# CH32V307RCT6-R1.net
KiCad netlist of a schematic drawn in Altium Designer
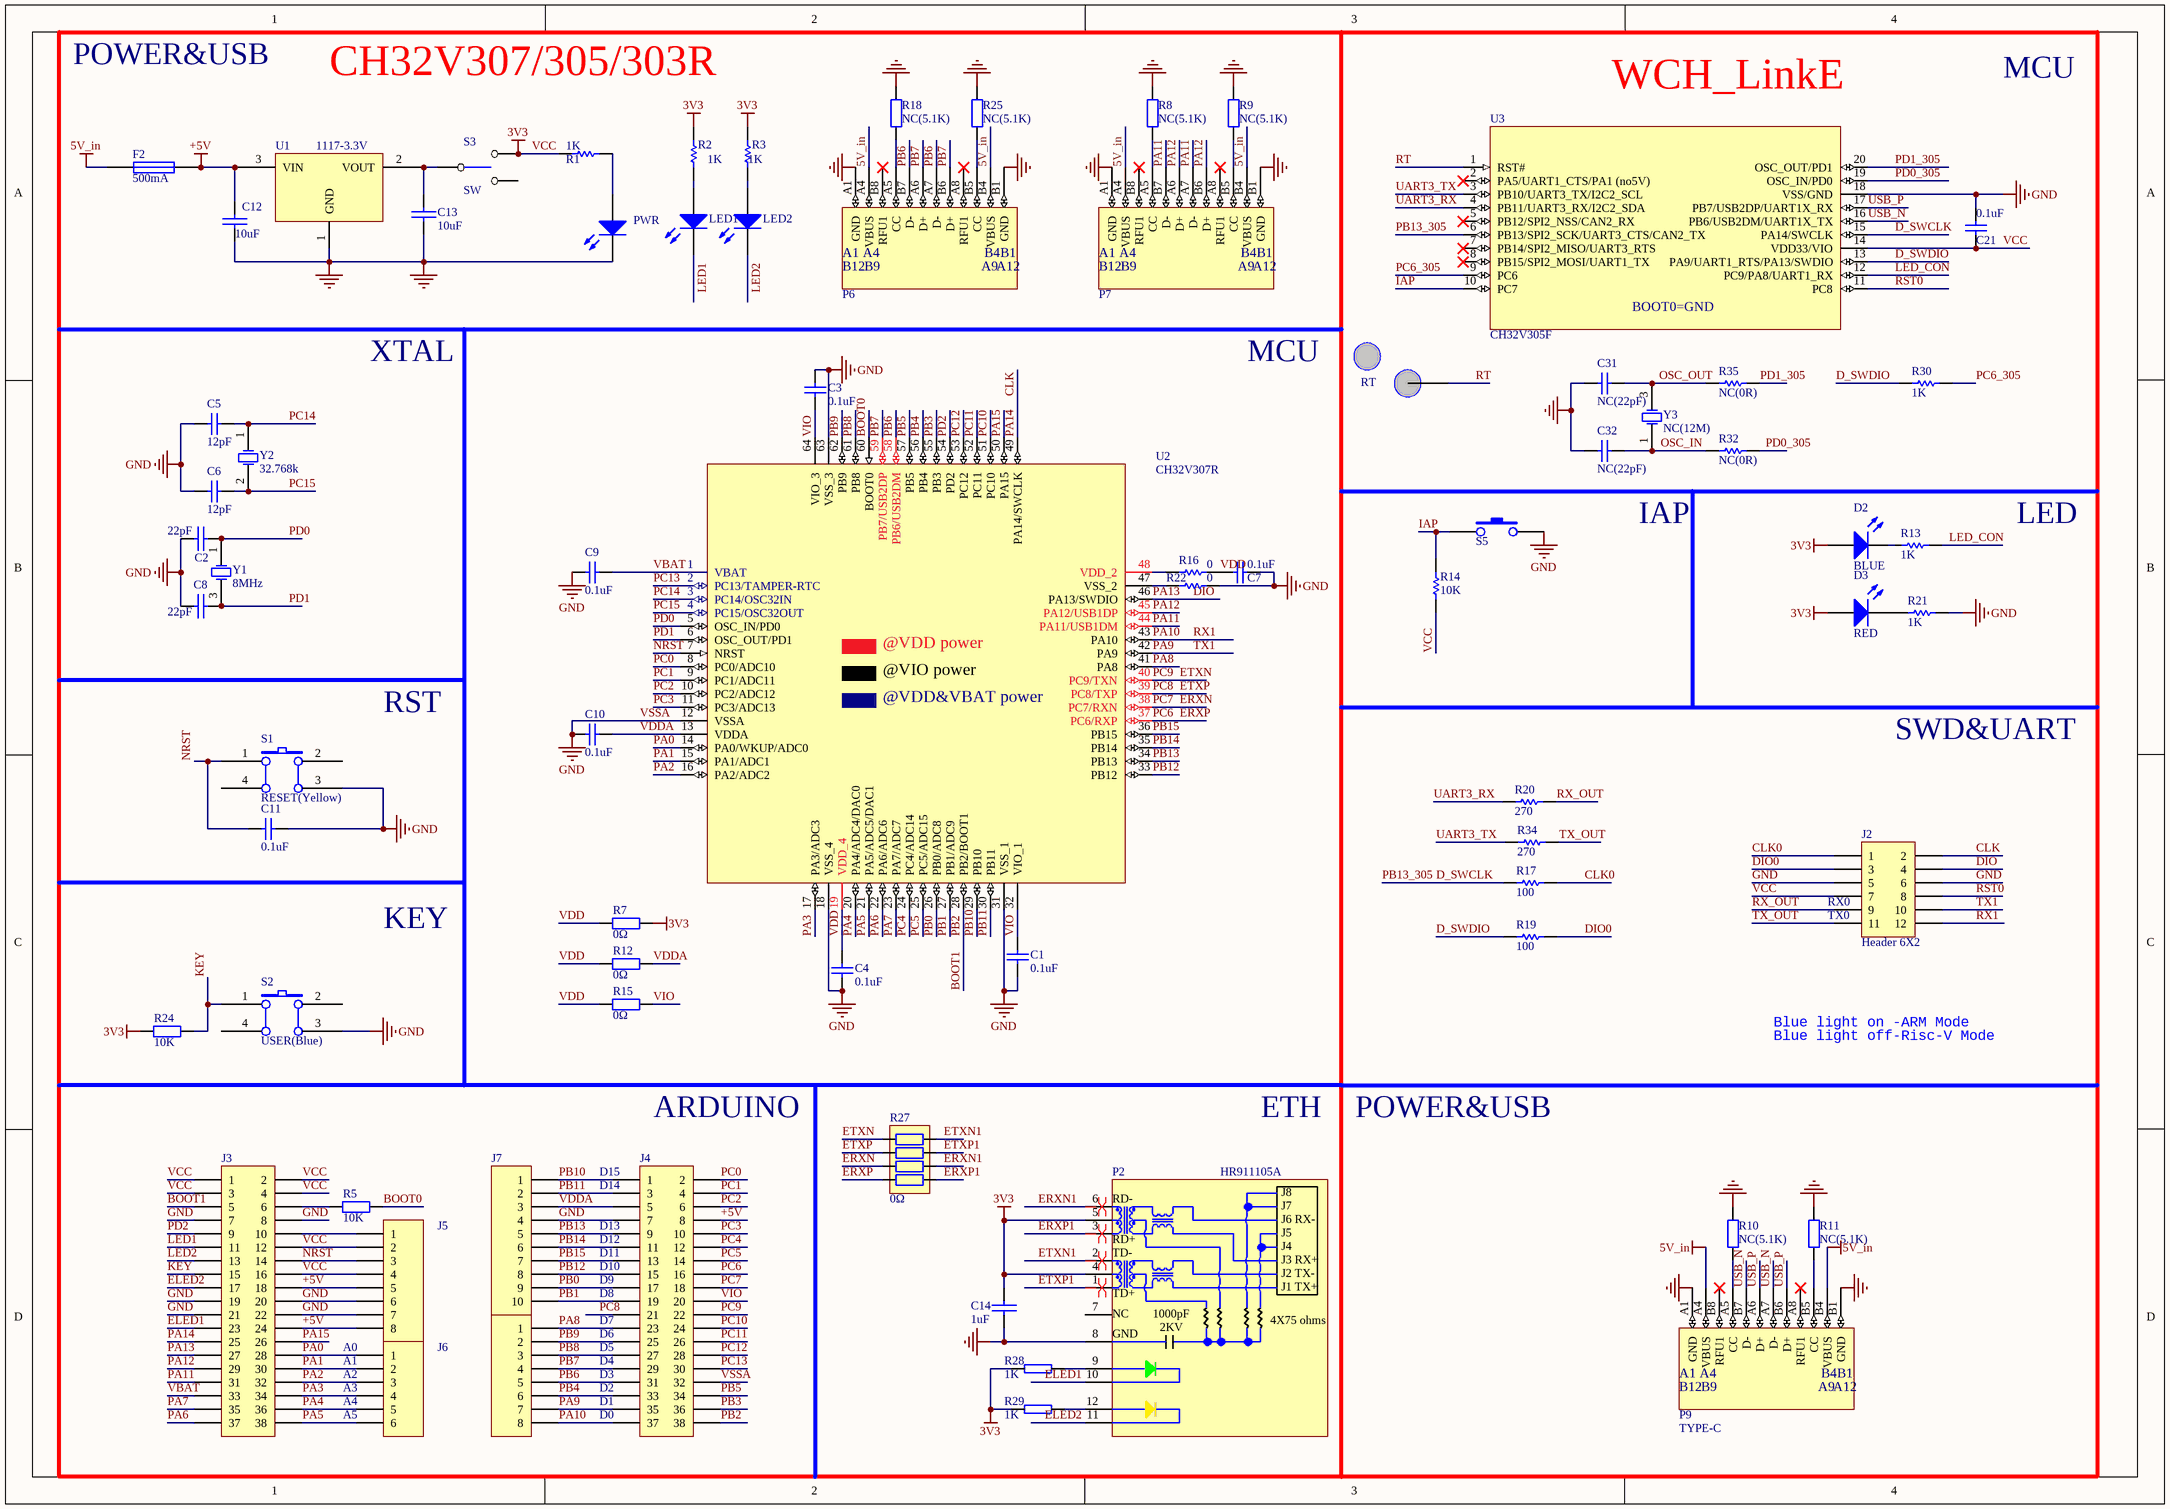
[diagram p0: CH32V307RCT6-R1.SchDoc]

(export (version "E")
  (design (tool "Eeschema 10.0.6"))
  (components
    (comp (ref "C1")
      (value "0.1uF")
      (footprint "0603_C")
      (description "Capacitor")
      (libsource (lib "Miscellaneous Devices") (part "Cap"))
    )
    (comp (ref "C2")
      (value "22pF")
      (footprint "0603_C")
      (description "Capacitor")
      (libsource (lib "*") (part "CAP"))
    )
    (comp (ref "C3")
      (value "0.1uF")
      (footprint "0603_C")
      (description "Capacitor")
      (libsource (lib "Miscellaneous Devices") (part "Cap"))
    )
    (comp (ref "C4")
      (value "0.1uF")
      (footprint "0603_C")
      (description "Capacitor")
      (libsource (lib "Miscellaneous Devices") (part "Cap"))
    )
    (comp (ref "C5")
      (value "12pF")
      (footprint "0603_C")
      (description "Capacitor")
      (libsource (lib "Miscellaneous Devices") (part "Cap"))
    )
    (comp (ref "C6")
      (value "12pF")
      (footprint "0603_C")
      (description "Capacitor")
      (libsource (lib "Miscellaneous Devices") (part "Cap"))
    )
    (comp (ref "C7")
      (value "0.1uF")
      (footprint "0603_C")
      (description "Capacitor")
      (libsource (lib "Miscellaneous Devices") (part "Cap"))
    )
    (comp (ref "C8")
      (value "22pF")
      (footprint "0603_C")
      (description "Capacitor")
      (libsource (lib "*") (part "CAP"))
    )
    (comp (ref "C9")
      (value "0.1uF")
      (footprint "0603_C")
      (description "Capacitor")
      (libsource (lib "Miscellaneous Devices") (part "Cap"))
    )
    (comp (ref "C10")
      (value "0.1uF")
      (footprint "0603_C")
      (description "Capacitor")
      (libsource (lib "Miscellaneous Devices") (part "Cap"))
    )
    (comp (ref "C11")
      (value "0.1uF")
      (footprint "0603_C")
      (description "Capacitor")
      (libsource (lib "Miscellaneous Devices") (part "Cap"))
    )
    (comp (ref "C12")
      (value "10uF")
      (footprint "3216_C")
      (description "Capacitor")
      (libsource (lib "*") (part "CAP"))
    )
    (comp (ref "C13")
      (value "10uF")
      (footprint "3216_C")
      (description "Capacitor")
      (libsource (lib "*") (part "CAP"))
    )
    (comp (ref "C14")
      (value "1uF")
      (footprint "0603_C")
      (description "Capacitor")
      (libsource (lib "*") (part "CAP"))
    )
    (comp (ref "C21")
      (value "0.1uF")
      (footprint "0603_C")
      (description "Capacitor")
      (libsource (lib "Miscellaneous Devices") (part "Cap"))
    )
    (comp (ref "C31")
      (value "NC(22pF)")
      (footprint "0603_C")
      (description "Capacitor")
      (fields (field (name "PUBLISHER") "Altium Limited"))
      (libsource (lib "*") (part "Cap"))
    )
    (comp (ref "C32")
      (value "NC(22pF)")
      (footprint "0603_C")
      (description "Capacitor")
      (fields (field (name "PUBLISHER") "Altium Limited"))
      (libsource (lib "*") (part "Cap"))
    )
    (comp (ref "D2")
      (value "BLUE")
      (footprint "0603+")
      (description "Typical RED, GREEN, YELLOW, AMBER GaAs LED")
      (fields (field (name "PUBLISHER") "Altium Limited"))
      (libsource (lib "MYLIB") (part "D0603"))
    )
    (comp (ref "D3")
      (value "RED")
      (footprint "0603+")
      (description "Typical RED, GREEN, YELLOW, AMBER GaAs LED")
      (fields (field (name "PUBLISHER") "Altium Limited"))
      (libsource (lib "MYLIB") (part "D0603"))
    )
    (comp (ref "F2")
      (value "500mA")
      (footprint "0805")
      (description "Fuse")
      (libsource (lib "*") (part "FUSE1"))
    )
    (comp (ref "J2")
      (value "Header 6X2")
      (footprint "IDC12-2.54mm")
      (description "Header, 6-Pin, Dual row")
      (fields (field (name "PUBLISHER") "Altium Limited"))
      (libsource (lib "Miscellaneous Connectors") (part "Header 6X2"))
    )
    (comp (ref "J3")
      (value "Header 19X2")
      (footprint "IDC38-2.54mm")
      (description "Header, 19-Pin, Dual row")
      (fields (field (name "PUBLISHER") "Altium Limited"))
      (libsource (lib "Miscellaneous Connectors") (part "Header 19X2"))
    )
    (comp (ref "J4")
      (value "Header 19X2")
      (footprint "IDC38-2.54mm")
      (description "Header, 19-Pin, Dual row")
      (fields (field (name "PUBLISHER") "Altium Limited"))
      (libsource (lib "Miscellaneous Connectors") (part "Header 19X2"))
    )
    (comp (ref "J5")
      (value "Header 8")
      (footprint "SIP8-2.54mm")
      (description "Header, 8-Pin")
      (fields (field (name "PUBLISHER") "Altium Limited"))
      (libsource (lib "Miscellaneous Connectors") (part "Header 8"))
    )
    (comp (ref "J6")
      (value "Header 6")
      (footprint "SIP6-2.54MM")
      (description "Header, 6-Pin")
      (fields (field (name "PUBLISHER") "Altium Limited"))
      (libsource (lib "Miscellaneous Connectors") (part "Header 6"))
    )
    (comp (ref "J7")
      (value "Header 10")
      (footprint "SIP10-2.54mm")
      (description "Header, 10-Pin")
      (fields (field (name "PUBLISHER") "Altium Limited"))
      (libsource (lib "Miscellaneous Connectors") (part "Header 10"))
    )
    (comp (ref "J8")
      (value "Header 8")
      (footprint "SIP8-2.54mm")
      (description "Header, 8-Pin")
      (fields (field (name "PUBLISHER") "Altium Limited"))
      (libsource (lib "") (part "Header 8_1"))
    )
    (comp (ref "LED1")
      (value "LED1   blue")
      (footprint "0603+")
      (description "Typical INFRARED GaAs LED")
      (fields (field (name "PUBLISHER") "Altium Limited"))
      (libsource (lib "Miscellaneous Devices") (part "LED0"))
    )
    (comp (ref "LED2")
      (value "LED2  blue")
      (footprint "0603+")
      (description "Typical INFRARED GaAs LED")
      (fields (field (name "PUBLISHER") "Altium Limited"))
      (libsource (lib "Miscellaneous Devices") (part "LED0"))
    )
    (comp (ref "P2") (value "HR911105A") (footprint "HR911105A") (libsource (lib "*") (part "HR911105A")))
    (comp (ref "P6")
      (value "TYPE-C")
      (footprint "TYPE-C-Receptacle-2.0")
      (libsource (lib "*") (part "TYPE-C1"))
    )
    (comp (ref "P7")
      (value "TYPE-C")
      (footprint "TYPE-C-Receptacle-2.0")
      (libsource (lib "*") (part "TYPE-C1"))
    )
    (comp (ref "P9")
      (value "TYPE-C")
      (footprint "TYPE-C-Receptacle-2.0")
      (libsource (lib "*") (part "TYPE-C1"))
    )
    (comp (ref "PWR")
      (value "POWER  red")
      (footprint "0603+")
      (description "Typical INFRARED GaAs LED")
      (fields (field (name "PUBLISHER") "Altium Limited"))
      (libsource (lib "Miscellaneous Devices") (part "LED0"))
    )
    (comp (ref "R1")
      (value "1K")
      (footprint "0603")
      (description "Semiconductor Resistor")
      (libsource (lib "Miscellaneous Devices") (part "Res Semi"))
    )
    (comp (ref "R2")
      (value "1K")
      (footprint "0603")
      (description "Semiconductor Resistor")
      (libsource (lib "Miscellaneous Devices") (part "Res Semi"))
    )
    (comp (ref "R3")
      (value "1K")
      (footprint "0603")
      (description "Semiconductor Resistor")
      (libsource (lib "Miscellaneous Devices") (part "Res Semi"))
    )
    (comp (ref "R5")
      (value "10K")
      (footprint "0603")
      (description "Resistor")
      (libsource (lib "") (part "Res2_3"))
    )
    (comp (ref "R7")
      (value "0Ω")
      (footprint "0603")
      (description "Resistor")
      (libsource (lib "Miscellaneous Devices") (part "Res2"))
    )
    (comp (ref "R8")
      (value "NC(5.1K)")
      (footprint "0603")
      (description "Resistor")
      (libsource (lib "") (part "Res2_2"))
    )
    (comp (ref "R9")
      (value "NC(5.1K)")
      (footprint "0603")
      (description "Resistor")
      (libsource (lib "") (part "Res2_2"))
    )
    (comp (ref "R10")
      (value "NC(5.1K)")
      (footprint "0603")
      (description "Resistor")
      (libsource (lib "") (part "Res2_1"))
    )
    (comp (ref "R11")
      (value "NC(5.1K)")
      (footprint "0603")
      (description "Resistor")
      (libsource (lib "") (part "Res2_1"))
    )
    (comp (ref "R12")
      (value "0Ω")
      (footprint "0603")
      (description "Resistor")
      (libsource (lib "Miscellaneous Devices") (part "Res2"))
    )
    (comp (ref "R13")
      (value "1K")
      (footprint "0603")
      (description "Resistor")
      (fields (field (name "PUBLISHER") "Altium Limited"))
      (libsource (lib "MYLIB") (part "0603-1"))
    )
    (comp (ref "R14")
      (value "10K")
      (footprint "0603")
      (description "Resistor")
      (fields (field (name "PUBLISHER") "Altium Limited"))
      (libsource (lib "MYLIB") (part "0603-1"))
    )
    (comp (ref "R15")
      (value "0Ω")
      (footprint "0603")
      (description "Resistor")
      (libsource (lib "Miscellaneous Devices") (part "Res2"))
    )
    (comp (ref "R16")
      (value "0")
      (footprint "0603")
      (description "Resistor")
      (fields (field (name "PUBLISHER") "Altium Limited"))
      (libsource (lib "MYLIB") (part "0603-1"))
    )
    (comp (ref "R17")
      (value "100")
      (footprint "0603")
      (description "Resistor")
      (fields (field (name "PUBLISHER") "Altium Limited"))
      (libsource (lib "MYLIB") (part "0603-1"))
    )
    (comp (ref "R18")
      (value "NC(5.1K)")
      (footprint "0603")
      (description "Resistor")
      (libsource (lib "") (part "Res2_2"))
    )
    (comp (ref "R19")
      (value "100")
      (footprint "0603")
      (description "Resistor")
      (fields (field (name "PUBLISHER") "Altium Limited"))
      (libsource (lib "MYLIB") (part "0603-1"))
    )
    (comp (ref "R20")
      (value "270")
      (footprint "0603")
      (description "Resistor")
      (fields (field (name "PUBLISHER") "Altium Limited"))
      (libsource (lib "MYLIB") (part "0603-1"))
    )
    (comp (ref "R21")
      (value "1K")
      (footprint "0603")
      (description "Resistor")
      (fields (field (name "PUBLISHER") "Altium Limited"))
      (libsource (lib "MYLIB") (part "0603-1"))
    )
    (comp (ref "R22")
      (value "0")
      (footprint "0603")
      (description "Resistor")
      (fields (field (name "PUBLISHER") "Altium Limited"))
      (libsource (lib "MYLIB") (part "0603-1"))
    )
    (comp (ref "R24")
      (value "10K")
      (footprint "0603")
      (description "Resistor")
      (libsource (lib "Miscellaneous Devices") (part "Res2"))
    )
    (comp (ref "R25")
      (value "NC(5.1K)")
      (footprint "0603")
      (description "Resistor")
      (libsource (lib "") (part "Res2_2"))
    )
    (comp (ref "R27")
      (value "0Ω")
      (footprint "8P4R-0603")
      (description "贴片网络排阻")
      (fields (field (name "版权归属") "源创客"))
      (libsource (lib "wch_sch_others") (part "R-8P4R"))
    )
    (comp (ref "R28") (value "1K") (footprint "0603") (libsource (lib "wch_sch_others") (part "RES")))
    (comp (ref "R29") (value "1K") (footprint "0603") (libsource (lib "wch_sch_others") (part "RES")))
    (comp (ref "R30")
      (value "1K")
      (footprint "0603")
      (description "Resistor")
      (fields (field (name "PUBLISHER") "Altium Limited"))
      (libsource (lib "MYLIB") (part "0603-1"))
    )
    (comp (ref "R32")
      (value "NC(0R)")
      (footprint "0603")
      (description "Resistor")
      (fields (field (name "PUBLISHER") "Altium Limited"))
      (libsource (lib "MYLIB") (part "0603-1"))
    )
    (comp (ref "R34")
      (value "270")
      (footprint "0603")
      (description "Resistor")
      (fields (field (name "PUBLISHER") "Altium Limited"))
      (libsource (lib "MYLIB") (part "0603-1"))
    )
    (comp (ref "R35")
      (value "NC(0R)")
      (footprint "0603")
      (description "Resistor")
      (fields (field (name "PUBLISHER") "Altium Limited"))
      (libsource (lib "MYLIB") (part "0603-1"))
    )
    (comp (ref "RT")
      (value "Testpoint")
      (footprint "TESTPOINT1")
      (description "测试点")
      (libsource (lib "wch_sch_others") (part "Testpoint"))
    )
    (comp (ref "S1")
      (value "RESET(Yellow)")
      (footprint "KEYX")
      (description "SE PUSHBUTTON")
      (libsource (lib "Documents") (part "SW PUSHBUTTON"))
    )
    (comp (ref "S2")
      (value "USER(Blue)")
      (footprint "KEYX")
      (description "SE PUSHBUTTON")
      (libsource (lib "Documents") (part "SW PUSHBUTTON"))
    )
    (comp (ref "S3") (value "SW") (footprint "SW1") (libsource (lib "MYSCH") (part "SW")))
    (comp (ref "S5") (value "KEY") (footprint "贴片按键") (libsource (lib "*") (part "KEY")))
    (comp (ref "U1")
      (value "1117-3.3V")
      (footprint "SOT-223")
      (libsource (lib "wch_sch_others") (part "1117-3.3V"))
    )
    (comp (ref "U2")
      (value "CH32V307R")
      (footprint "LQFP64M_10x10")
      (description "RISC-V FPU HD-MCU, 144MHz, USB_480M, USB OTG, 1000M Ethernet MAC, 2*CAN")
      (libsource (lib "CHXXX") (part "CH32V307R"))
    )
    (comp (ref "U3")
      (value "CH32V305F")
      (footprint "TSSOP20")
      (description "RISC-V FPU HD-MCU, 144MHz, USB_480M, CAN, UART*2, SPI")
      (libsource (lib "CHXXX") (part "CH32V305F"))
    )
    (comp (ref "Y1")
      (value "8MHz")
      (footprint "XT3225")
      (description "Crystal Oscillator")
      (fields (field (name "PUBLISHER") "Altium Limited"))
      (libsource (lib "*") (part "XTAL"))
    )
    (comp (ref "Y2")
      (value "32.768k")
      (footprint "FC-135")
      (description "Crystal Oscillator")
      (fields (field (name "PUBLISHER") "Altium Limited"))
      (libsource (lib "Miscellaneous Devices") (part "XTAL"))
    )
    (comp (ref "Y3")
      (value "NC(12M)")
      (footprint "XT3225")
      (description "Crystal Oscillator")
      (libsource (lib "*") (part "XTAL"))
    )
  )
  (nets
    (net (code "1") (name "+5V") (class "Default")
      (node (ref "C12") (pin "1") (pinfunction "1_1") (pintype "passive"))
      (node (ref "F2") (pin "2") (pinfunction "2_2") (pintype "passive"))
      (node (ref "J3") (pin "18") (pinfunction "18_18") (pintype "passive"))
      (node (ref "J3") (pin "24") (pinfunction "24_24") (pintype "passive"))
      (node (ref "J4") (pin "8") (pinfunction "8_8") (pintype "passive"))
      (node (ref "J5") (pin "5") (pinfunction "5_5") (pintype "passive"))
      (node (ref "J5") (pin "8") (pinfunction "8_8") (pintype "passive"))
      (node (ref "U1") (pin "3") (pinfunction "VIN_3") (pintype "passive"))
    )
    (net (code "2") (name "/BOOT0") (class "Default")
      (node (ref "R5") (pin "2") (pinfunction "2_2") (pintype "passive"))
      (node (ref "U2") (pin "60") (pinfunction "BOOT0_60") (pintype "input"))
    )
    (net (code "3") (name "/BOOT1") (class "Default")
      (node (ref "J3") (pin "5") (pinfunction "5_5") (pintype "passive"))
      (node (ref "J4") (pin "38") (pinfunction "38_38") (pintype "passive"))
      (node (ref "U2") (pin "28") (pinfunction "PB2/BOOT1_28") (pintype "bidirectional"))
    )
    (net (code "4") (name "/CLK") (class "Default")
      (node (ref "J2") (pin "2") (pinfunction "2_2") (pintype "passive"))
      (node (ref "J3") (pin "25") (pinfunction "25_25") (pintype "passive"))
      (node (ref "U2") (pin "49") (pinfunction "PA14/SWCLK_49") (pintype "bidirectional"))
    )
    (net (code "5") (name "/CLK0") (class "Default")
      (node (ref "J2") (pin "1") (pinfunction "1_1") (pintype "passive"))
      (node (ref "R17") (pin "1") (pinfunction "1_1") (pintype "passive"))
    )
    (net (code "6") (name "/DIO") (class "Default")
      (node (ref "J2") (pin "4") (pinfunction "4_4") (pintype "passive"))
      (node (ref "J3") (pin "27") (pinfunction "27_27") (pintype "passive"))
      (node (ref "U2") (pin "46") (pinfunction "PA13/SWDIO_46") (pintype "bidirectional"))
    )
    (net (code "7") (name "/DIO0") (class "Default")
      (node (ref "J2") (pin "3") (pinfunction "3_3") (pintype "passive"))
      (node (ref "R19") (pin "1") (pinfunction "1_1") (pintype "passive"))
    )
    (net (code "8") (name "/D_SWCLK") (class "Default")
      (node (ref "R17") (pin "2") (pinfunction "2_2") (pintype "passive"))
      (node (ref "U3") (pin "15") (pinfunction "PA14/SWCLK_15") (pintype "bidirectional"))
      (node (ref "U3") (pin "6") (pinfunction "PB13/SPI2_SCK/UART3_CTS/CAN2_TX_6") (pintype "bidirectional"))
    )
    (net (code "9") (name "/D_SWDIO") (class "Default")
      (node (ref "R19") (pin "2") (pinfunction "2_2") (pintype "passive"))
      (node (ref "R30") (pin "1") (pinfunction "1_1") (pintype "passive"))
      (node (ref "U3") (pin "13") (pinfunction "PA9/UART1_RTS/PA13/SWDIO_13") (pintype "bidirectional"))
    )
    (net (code "10") (name "/ELED1") (class "Default")
      (node (ref "J3") (pin "23") (pinfunction "23_23") (pintype "passive"))
      (node (ref "P2") (pin "10") (pintype "passive"))
    )
    (net (code "11") (name "/ELED2") (class "Default")
      (node (ref "J3") (pin "17") (pinfunction "17_17") (pintype "passive"))
      (node (ref "P2") (pin "11") (pintype "passive"))
    )
    (net (code "12") (name "/ERXN") (class "Default")
      (node (ref "J4") (pin "18") (pinfunction "18_18") (pintype "passive"))
      (node (ref "R27") (pin "3") (pinfunction "3_3") (pintype "passive"))
      (node (ref "U2") (pin "38") (pinfunction "PC7/RXN_38") (pintype "bidirectional"))
    )
    (net (code "13") (name "/ERXN1") (class "Default")
      (node (ref "P2") (pin "6") (pintype "passive"))
      (node (ref "R27") (pin "6") (pinfunction "6_6") (pintype "passive"))
    )
    (net (code "14") (name "/ERXP") (class "Default")
      (node (ref "J4") (pin "16") (pinfunction "16_16") (pintype "passive"))
      (node (ref "R27") (pin "4") (pinfunction "4_4") (pintype "passive"))
      (node (ref "U2") (pin "37") (pinfunction "PC6/RXP_37") (pintype "bidirectional"))
    )
    (net (code "15") (name "/ERXP1") (class "Default")
      (node (ref "P2") (pin "3") (pintype "passive"))
      (node (ref "R27") (pin "5") (pinfunction "5_5") (pintype "passive"))
    )
    (net (code "16") (name "/ETXN") (class "Default")
      (node (ref "J4") (pin "22") (pinfunction "22_22") (pintype "passive"))
      (node (ref "R27") (pin "1") (pinfunction "1_1") (pintype "passive"))
      (node (ref "U2") (pin "40") (pinfunction "PC9/TXN_40") (pintype "bidirectional"))
    )
    (net (code "17") (name "/ETXN1") (class "Default")
      (node (ref "P2") (pin "2") (pintype "passive"))
      (node (ref "R27") (pin "8") (pinfunction "8_8") (pintype "passive"))
    )
    (net (code "18") (name "/ETXP") (class "Default")
      (node (ref "J4") (pin "21") (pinfunction "21_21") (pintype "passive"))
      (node (ref "R27") (pin "2") (pinfunction "2_2") (pintype "passive"))
      (node (ref "U2") (pin "39") (pinfunction "PC8/TXP_39") (pintype "bidirectional"))
    )
    (net (code "19") (name "/ETXP1") (class "Default")
      (node (ref "P2") (pin "1") (pintype "passive"))
      (node (ref "R27") (pin "7") (pinfunction "7_7") (pintype "passive"))
    )
    (net (code "20") (name "/IAP") (class "Default")
      (node (ref "R14") (pin "1") (pinfunction "1_1") (pintype "passive"))
      (node (ref "S5") (pin "1") (pinfunction "1_1") (pintype "passive"))
      (node (ref "U3") (pin "10") (pinfunction "PC7_10") (pintype "bidirectional"))
    )
    (net (code "21") (name "/KEY") (class "Default")
      (node (ref "J3") (pin "15") (pinfunction "15_15") (pintype "passive"))
      (node (ref "R24") (pin "1") (pinfunction "1_1") (pintype "passive"))
      (node (ref "S2") (pin "1") (pinfunction "A0_1") (pintype "passive"))
    )
    (net (code "22") (name "/LED1") (class "Default")
      (node (ref "J3") (pin "11") (pinfunction "11_11") (pintype "passive"))
      (node (ref "LED1") (pin "2") (pinfunction "K_2") (pintype "passive"))
    )
    (net (code "23") (name "/LED2") (class "Default")
      (node (ref "J3") (pin "13") (pinfunction "13_13") (pintype "passive"))
      (node (ref "LED2") (pin "2") (pinfunction "K_2") (pintype "passive"))
    )
    (net (code "24") (name "/LED_CON") (class "Default")
      (node (ref "R13") (pin "1") (pinfunction "1_1") (pintype "passive"))
      (node (ref "U3") (pin "12") (pinfunction "PC9/PA8/UART1_RX_12") (pintype "bidirectional"))
    )
    (net (code "25") (name "/NRST") (class "Default")
      (node (ref "C11") (pin "2") (pinfunction "2_2") (pintype "passive"))
      (node (ref "J3") (pin "14") (pinfunction "14_14") (pintype "passive"))
      (node (ref "J5") (pin "3") (pinfunction "3_3") (pintype "passive"))
      (node (ref "S1") (pin "1") (pinfunction "A0_1") (pintype "passive"))
      (node (ref "U2") (pin "7") (pinfunction "NRST_7") (pintype "input"))
    )
    (net (code "26") (name "/OSC_IN") (class "Default")
      (node (ref "C32") (pin "2") (pinfunction "2_2") (pintype "passive"))
      (node (ref "R32") (pin "2") (pinfunction "2_2") (pintype "passive"))
      (node (ref "Y3") (pin "1") (pinfunction "OSC1_1") (pintype "passive"))
    )
    (net (code "27") (name "/OSC_OUT") (class "Default")
      (node (ref "C31") (pin "2") (pinfunction "2_2") (pintype "passive"))
      (node (ref "R35") (pin "2") (pinfunction "2_2") (pintype "passive"))
      (node (ref "Y3") (pin "3") (pinfunction "OSC2_3") (pintype "passive"))
    )
    (net (code "28") (name "/PA0") (class "Default")
      (node (ref "J3") (pin "28") (pinfunction "28_28") (pintype "passive"))
      (node (ref "J6") (pin "1") (pinfunction "1_1") (pintype "passive"))
      (node (ref "U2") (pin "14") (pinfunction "PA0/WKUP/ADC0_14") (pintype "bidirectional"))
    )
    (net (code "29") (name "/PA1") (class "Default")
      (node (ref "J3") (pin "30") (pinfunction "30_30") (pintype "passive"))
      (node (ref "J6") (pin "2") (pinfunction "2_2") (pintype "passive"))
      (node (ref "U2") (pin "15") (pinfunction "PA1/ADC1_15") (pintype "bidirectional"))
    )
    (net (code "30") (name "/PA2") (class "Default")
      (node (ref "J3") (pin "32") (pinfunction "32_32") (pintype "passive"))
      (node (ref "J6") (pin "3") (pinfunction "3_3") (pintype "passive"))
      (node (ref "U2") (pin "16") (pinfunction "PA2/ADC2_16") (pintype "bidirectional"))
    )
    (net (code "31") (name "/PA3") (class "Default")
      (node (ref "J3") (pin "34") (pinfunction "34_34") (pintype "passive"))
      (node (ref "J6") (pin "4") (pinfunction "4_4") (pintype "passive"))
      (node (ref "U2") (pin "17") (pinfunction "PA3/ADC3_17") (pintype "bidirectional"))
    )
    (net (code "32") (name "/PA4") (class "Default")
      (node (ref "J3") (pin "36") (pinfunction "36_36") (pintype "passive"))
      (node (ref "J6") (pin "5") (pinfunction "5_5") (pintype "passive"))
      (node (ref "U2") (pin "20") (pinfunction "PA4/ADC4/DAC0_20") (pintype "bidirectional"))
    )
    (net (code "33") (name "/PA5") (class "Default")
      (node (ref "J3") (pin "38") (pinfunction "38_38") (pintype "passive"))
      (node (ref "J6") (pin "6") (pinfunction "6_6") (pintype "passive"))
      (node (ref "U2") (pin "21") (pinfunction "PA5/ADC5/DAC1_21") (pintype "bidirectional"))
    )
    (net (code "34") (name "/PA6") (class "Default")
      (node (ref "J3") (pin "37") (pinfunction "37_37") (pintype "passive"))
      (node (ref "U2") (pin "22") (pinfunction "PA6/ADC6_22") (pintype "bidirectional"))
    )
    (net (code "35") (name "/PA7") (class "Default")
      (node (ref "J3") (pin "35") (pinfunction "35_35") (pintype "passive"))
      (node (ref "U2") (pin "23") (pinfunction "PA7/ADC7_23") (pintype "bidirectional"))
    )
    (net (code "36") (name "/PA8") (class "Default")
      (node (ref "J4") (pin "23") (pinfunction "23_23") (pintype "passive"))
      (node (ref "J8") (pin "1") (pinfunction "1_1") (pintype "passive"))
      (node (ref "U2") (pin "41") (pinfunction "PA8_41") (pintype "bidirectional"))
    )
    (net (code "37") (name "/PA9") (class "Default")
      (node (ref "J2") (pin "10") (pinfunction "10_10") (pintype "passive"))
      (node (ref "J4") (pin "35") (pinfunction "35_35") (pintype "passive"))
      (node (ref "J8") (pin "7") (pinfunction "7_7") (pintype "passive"))
      (node (ref "U2") (pin "42") (pinfunction "PA9_42") (pintype "bidirectional"))
    )
    (net (code "38") (name "/PA10") (class "Default")
      (node (ref "J2") (pin "12") (pinfunction "12_12") (pintype "passive"))
      (node (ref "J4") (pin "37") (pinfunction "37_37") (pintype "passive"))
      (node (ref "J8") (pin "8") (pinfunction "8_8") (pintype "passive"))
      (node (ref "U2") (pin "43") (pinfunction "PA10_43") (pintype "bidirectional"))
    )
    (net (code "39") (name "/PA11") (class "Default")
      (node (ref "J3") (pin "31") (pinfunction "31_31") (pintype "passive"))
      (node (ref "P7") (pin "A7") (pinfunction "D-_A7") (pintype "bidirectional"))
      (node (ref "P7") (pin "B7") (pinfunction "D-_B7") (pintype "bidirectional"))
      (node (ref "U2") (pin "44") (pinfunction "PA11/USB1DM_44") (pintype "bidirectional"))
    )
    (net (code "40") (name "/PA12") (class "Default")
      (node (ref "J3") (pin "29") (pinfunction "29_29") (pintype "passive"))
      (node (ref "P7") (pin "A6") (pinfunction "D+_A6") (pintype "bidirectional"))
      (node (ref "P7") (pin "B6") (pinfunction "D+_B6") (pintype "bidirectional"))
      (node (ref "U2") (pin "45") (pinfunction "PA12/USB1DP_45") (pintype "bidirectional"))
    )
    (net (code "41") (name "/PA15") (class "Default")
      (node (ref "J3") (pin "26") (pinfunction "26_26") (pintype "passive"))
      (node (ref "U2") (pin "50") (pinfunction "PA15_50") (pintype "bidirectional"))
    )
    (net (code "42") (name "/PB0") (class "Default")
      (node (ref "J4") (pin "17") (pinfunction "17_17") (pintype "passive"))
      (node (ref "J7") (pin "9") (pinfunction "9_9") (pintype "passive"))
      (node (ref "U2") (pin "26") (pinfunction "PB0/ADC8_26") (pintype "bidirectional"))
    )
    (net (code "43") (name "/PB1") (class "Default")
      (node (ref "J4") (pin "19") (pinfunction "19_19") (pintype "passive"))
      (node (ref "J7") (pin "10") (pinfunction "10_10") (pintype "passive"))
      (node (ref "U2") (pin "27") (pinfunction "PB1/ADC9_27") (pintype "bidirectional"))
    )
    (net (code "44") (name "/PB3") (class "Default")
      (node (ref "J4") (pin "36") (pinfunction "36_36") (pintype "passive"))
      (node (ref "U2") (pin "55") (pinfunction "PB3_55") (pintype "bidirectional"))
    )
    (net (code "45") (name "/PB4") (class "Default")
      (node (ref "J4") (pin "33") (pinfunction "33_33") (pintype "passive"))
      (node (ref "J8") (pin "6") (pinfunction "6_6") (pintype "passive"))
      (node (ref "U2") (pin "56") (pinfunction "PB4_56") (pintype "bidirectional"))
    )
    (net (code "46") (name "/PB5") (class "Default")
      (node (ref "J4") (pin "34") (pinfunction "34_34") (pintype "passive"))
      (node (ref "U2") (pin "57") (pinfunction "PB5_57") (pintype "bidirectional"))
    )
    (net (code "47") (name "/PB6") (class "Default")
      (node (ref "J4") (pin "31") (pinfunction "31_31") (pintype "passive"))
      (node (ref "J8") (pin "5") (pinfunction "5_5") (pintype "passive"))
      (node (ref "P6") (pin "A7") (pinfunction "D-_A7") (pintype "bidirectional"))
      (node (ref "P6") (pin "B7") (pinfunction "D-_B7") (pintype "bidirectional"))
      (node (ref "U2") (pin "58") (pinfunction "PB6/USB2DM_58") (pintype "bidirectional"))
    )
    (net (code "48") (name "/PB7") (class "Default")
      (node (ref "J4") (pin "29") (pinfunction "29_29") (pintype "passive"))
      (node (ref "J8") (pin "4") (pinfunction "4_4") (pintype "passive"))
      (node (ref "P6") (pin "A6") (pinfunction "D+_A6") (pintype "bidirectional"))
      (node (ref "P6") (pin "B6") (pinfunction "D+_B6") (pintype "bidirectional"))
      (node (ref "U2") (pin "59") (pinfunction "PB7/USB2DP_59") (pintype "bidirectional"))
    )
    (net (code "49") (name "/PB8") (class "Default")
      (node (ref "J4") (pin "27") (pinfunction "27_27") (pintype "passive"))
      (node (ref "J8") (pin "3") (pinfunction "3_3") (pintype "passive"))
      (node (ref "U2") (pin "61") (pinfunction "PB8_61") (pintype "bidirectional"))
    )
    (net (code "50") (name "/PB9") (class "Default")
      (node (ref "J4") (pin "25") (pinfunction "25_25") (pintype "passive"))
      (node (ref "J8") (pin "2") (pinfunction "2_2") (pintype "passive"))
      (node (ref "U2") (pin "62") (pinfunction "PB9_62") (pintype "bidirectional"))
    )
    (net (code "51") (name "/PB10") (class "Default")
      (node (ref "J4") (pin "1") (pinfunction "1_1") (pintype "passive"))
      (node (ref "J7") (pin "1") (pinfunction "1_1") (pintype "passive"))
      (node (ref "U2") (pin "29") (pinfunction "PB10_29") (pintype "bidirectional"))
    )
    (net (code "52") (name "/PB11") (class "Default")
      (node (ref "J4") (pin "3") (pinfunction "3_3") (pintype "passive"))
      (node (ref "J7") (pin "2") (pinfunction "2_2") (pintype "passive"))
      (node (ref "U2") (pin "30") (pinfunction "PB11_30") (pintype "bidirectional"))
    )
    (net (code "53") (name "/PB12") (class "Default")
      (node (ref "J4") (pin "15") (pinfunction "15_15") (pintype "passive"))
      (node (ref "J7") (pin "8") (pinfunction "8_8") (pintype "passive"))
      (node (ref "U2") (pin "33") (pinfunction "PB12_33") (pintype "bidirectional"))
    )
    (net (code "54") (name "/PB13") (class "Default")
      (node (ref "J4") (pin "9") (pinfunction "9_9") (pintype "passive"))
      (node (ref "J7") (pin "5") (pinfunction "5_5") (pintype "passive"))
      (node (ref "U2") (pin "34") (pinfunction "PB13_34") (pintype "bidirectional"))
    )
    (net (code "55") (name "/PB14") (class "Default")
      (node (ref "J4") (pin "11") (pinfunction "11_11") (pintype "passive"))
      (node (ref "J7") (pin "6") (pinfunction "6_6") (pintype "passive"))
      (node (ref "U2") (pin "35") (pinfunction "PB14_35") (pintype "bidirectional"))
    )
    (net (code "56") (name "/PB15") (class "Default")
      (node (ref "J4") (pin "13") (pinfunction "13_13") (pintype "passive"))
      (node (ref "J7") (pin "7") (pinfunction "7_7") (pintype "passive"))
      (node (ref "U2") (pin "36") (pinfunction "PB15_36") (pintype "bidirectional"))
    )
    (net (code "57") (name "/PC0") (class "Default")
      (node (ref "J4") (pin "2") (pinfunction "2_2") (pintype "passive"))
      (node (ref "U2") (pin "8") (pinfunction "PC0/ADC10_8") (pintype "bidirectional"))
    )
    (net (code "58") (name "/PC1") (class "Default")
      (node (ref "J4") (pin "4") (pinfunction "4_4") (pintype "passive"))
      (node (ref "U2") (pin "9") (pinfunction "PC1/ADC11_9") (pintype "bidirectional"))
    )
    (net (code "59") (name "/PC2") (class "Default")
      (node (ref "J4") (pin "6") (pinfunction "6_6") (pintype "passive"))
      (node (ref "U2") (pin "10") (pinfunction "PC2/ADC12_10") (pintype "bidirectional"))
    )
    (net (code "60") (name "/PC3") (class "Default")
      (node (ref "J4") (pin "10") (pinfunction "10_10") (pintype "passive"))
      (node (ref "U2") (pin "11") (pinfunction "PC3/ADC13_11") (pintype "bidirectional"))
    )
    (net (code "61") (name "/PC4") (class "Default")
      (node (ref "J4") (pin "12") (pinfunction "12_12") (pintype "passive"))
      (node (ref "U2") (pin "24") (pinfunction "PC4/ADC14_24") (pintype "bidirectional"))
    )
    (net (code "62") (name "/PC5") (class "Default")
      (node (ref "J4") (pin "14") (pinfunction "14_14") (pintype "passive"))
      (node (ref "U2") (pin "25") (pinfunction "PC5/ADC15_25") (pintype "bidirectional"))
    )
    (net (code "63") (name "/PC6_305") (class "Default")
      (node (ref "R30") (pin "2") (pinfunction "2_2") (pintype "passive"))
      (node (ref "U3") (pin "9") (pinfunction "PC6_9") (pintype "bidirectional"))
    )
    (net (code "64") (name "/PC10") (class "Default")
      (node (ref "J4") (pin "24") (pinfunction "24_24") (pintype "passive"))
      (node (ref "U2") (pin "51") (pinfunction "PC10_51") (pintype "bidirectional"))
    )
    (net (code "65") (name "/PC11") (class "Default")
      (node (ref "J4") (pin "26") (pinfunction "26_26") (pintype "passive"))
      (node (ref "U2") (pin "52") (pinfunction "PC11_52") (pintype "bidirectional"))
    )
    (net (code "66") (name "/PC12") (class "Default")
      (node (ref "J4") (pin "28") (pinfunction "28_28") (pintype "passive"))
      (node (ref "U2") (pin "53") (pinfunction "PC12_53") (pintype "bidirectional"))
    )
    (net (code "67") (name "/PC13") (class "Default")
      (node (ref "J4") (pin "30") (pinfunction "30_30") (pintype "passive"))
      (node (ref "U2") (pin "2") (pinfunction "PC13/TAMPER-RTC_2") (pintype "bidirectional"))
    )
    (net (code "68") (name "/PC14") (class "Default")
      (node (ref "C5") (pin "1") (pinfunction "1_1") (pintype "passive"))
      (node (ref "U2") (pin "3") (pinfunction "PC14/OSC32IN_3") (pintype "bidirectional"))
      (node (ref "Y2") (pin "1") (pinfunction "OSC1_1") (pintype "passive"))
    )
    (net (code "69") (name "/PC15") (class "Default")
      (node (ref "C6") (pin "1") (pinfunction "1_1") (pintype "passive"))
      (node (ref "U2") (pin "4") (pinfunction "PC15/OSC32OUT_4") (pintype "bidirectional"))
      (node (ref "Y2") (pin "2") (pinfunction "OSC2_2") (pintype "passive"))
    )
    (net (code "70") (name "/PD0") (class "Default")
      (node (ref "C2") (pin "2") (pinfunction "2_2") (pintype "passive"))
      (node (ref "U2") (pin "5") (pinfunction "OSC_IN/PD0_5") (pintype "bidirectional"))
      (node (ref "Y1") (pin "1") (pinfunction "OSC1_1") (pintype "passive"))
    )
    (net (code "71") (name "/PD0_305") (class "Default")
      (node (ref "R32") (pin "1") (pinfunction "1_1") (pintype "passive"))
      (node (ref "U3") (pin "19") (pinfunction "OSC_IN/PD0_19") (pintype "bidirectional"))
    )
    (net (code "72") (name "/PD1") (class "Default")
      (node (ref "C8") (pin "2") (pinfunction "2_2") (pintype "passive"))
      (node (ref "U2") (pin "6") (pinfunction "OSC_OUT/PD1_6") (pintype "bidirectional"))
      (node (ref "Y1") (pin "3") (pinfunction "OSC2_3") (pintype "passive"))
    )
    (net (code "73") (name "/PD1_305") (class "Default")
      (node (ref "R35") (pin "1") (pinfunction "1_1") (pintype "passive"))
      (node (ref "U3") (pin "20") (pinfunction "OSC_OUT/PD1_20") (pintype "bidirectional"))
    )
    (net (code "74") (name "/PD2") (class "Default")
      (node (ref "J3") (pin "9") (pinfunction "9_9") (pintype "passive"))
      (node (ref "U2") (pin "54") (pinfunction "PD2_54") (pintype "bidirectional"))
    )
    (net (code "75") (name "/RST0") (class "Default")
      (node (ref "J2") (pin "8") (pinfunction "8_8") (pintype "passive"))
      (node (ref "U3") (pin "11") (pinfunction "PC8_11") (pintype "bidirectional"))
    )
    (net (code "76") (name "/RT") (class "Default")
      (node (ref "RT") (pin "1") (pinfunction "point_1") (pintype "passive"))
      (node (ref "U3") (pin "1") (pinfunction "RST#_1") (pintype "input"))
    )
    (net (code "77") (name "/RX_OUT") (class "Default")
      (node (ref "J2") (pin "9") (pinfunction "9_9") (pintype "passive"))
      (node (ref "R20") (pin "1") (pinfunction "1_1") (pintype "passive"))
    )
    (net (code "78") (name "/TX_OUT") (class "Default")
      (node (ref "J2") (pin "11") (pinfunction "11_11") (pintype "passive"))
      (node (ref "R34") (pin "1") (pinfunction "1_1") (pintype "passive"))
    )
    (net (code "79") (name "/UART3_RX") (class "Default")
      (node (ref "R20") (pin "2") (pinfunction "2_2") (pintype "passive"))
      (node (ref "U3") (pin "4") (pinfunction "PB11/UART3_RX/I2C2_SDA_4") (pintype "bidirectional"))
    )
    (net (code "80") (name "/UART3_TX") (class "Default")
      (node (ref "R34") (pin "2") (pinfunction "2_2") (pintype "passive"))
      (node (ref "U3") (pin "3") (pinfunction "PB10/UART3_TX/I2C2_SCL_3") (pintype "bidirectional"))
    )
    (net (code "81") (name "/USB_N") (class "Default")
      (node (ref "P9") (pin "A7") (pinfunction "D-_A7") (pintype "bidirectional"))
      (node (ref "P9") (pin "B7") (pinfunction "D-_B7") (pintype "bidirectional"))
      (node (ref "U3") (pin "16") (pinfunction "PB6/USB2DM/UART1X_TX_16") (pintype "bidirectional"))
    )
    (net (code "82") (name "/USB_P") (class "Default")
      (node (ref "P9") (pin "A6") (pinfunction "D+_A6") (pintype "bidirectional"))
      (node (ref "P9") (pin "B6") (pinfunction "D+_B6") (pintype "bidirectional"))
      (node (ref "U3") (pin "17") (pinfunction "PB7/USB2DP/UART1X_RX_17") (pintype "bidirectional"))
    )
    (net (code "83") (name "/VBAT") (class "Default")
      (node (ref "C9") (pin "1") (pinfunction "1_1") (pintype "passive"))
      (node (ref "J3") (pin "33") (pinfunction "33_33") (pintype "passive"))
      (node (ref "U2") (pin "1") (pinfunction "VBAT_1") (pintype "power_in"))
    )
    (net (code "84") (name "/VDD") (class "Default")
      (node (ref "C4") (pin "2") (pinfunction "2_2") (pintype "passive"))
      (node (ref "C7") (pin "2") (pinfunction "2_2") (pintype "passive"))
      (node (ref "R12") (pin "2") (pinfunction "2_2") (pintype "passive"))
      (node (ref "R15") (pin "2") (pinfunction "2_2") (pintype "passive"))
      (node (ref "R16") (pin "1") (pinfunction "1_1") (pintype "passive"))
      (node (ref "R7") (pin "2") (pinfunction "2_2") (pintype "passive"))
      (node (ref "U2") (pin "19") (pinfunction "VDD_4_19") (pintype "power_in"))
    )
    (net (code "85") (name "/VDDA") (class "Default")
      (node (ref "C10") (pin "1") (pinfunction "1_1") (pintype "passive"))
      (node (ref "J4") (pin "5") (pinfunction "5_5") (pintype "passive"))
      (node (ref "J7") (pin "3") (pinfunction "3_3") (pintype "passive"))
      (node (ref "R12") (pin "1") (pinfunction "1_1") (pintype "passive"))
      (node (ref "U2") (pin "13") (pinfunction "VDDA_13") (pintype "power_in"))
    )
    (net (code "86") (name "/VIO") (class "Default")
      (node (ref "C1") (pin "2") (pinfunction "2_2") (pintype "passive"))
      (node (ref "C3") (pin "2") (pinfunction "2_2") (pintype "passive"))
      (node (ref "J4") (pin "20") (pinfunction "20_20") (pintype "passive"))
      (node (ref "R15") (pin "1") (pinfunction "1_1") (pintype "passive"))
      (node (ref "U2") (pin "32") (pinfunction "VIO_1_32") (pintype "power_in"))
      (node (ref "U2") (pin "64") (pinfunction "VIO_3_64") (pintype "power_in"))
    )
    (net (code "87") (name "3V3") (class "Default")
      (node (ref "C14") (pin "2") (pinfunction "2_2") (pintype "passive"))
      (node (ref "C21") (pin "1") (pinfunction "1_1") (pintype "passive"))
      (node (ref "D2") (pin "1") (pinfunction "A_1") (pintype "passive"))
      (node (ref "D3") (pin "1") (pinfunction "A_1") (pintype "passive"))
      (node (ref "J2") (pin "7") (pinfunction "7_7") (pintype "passive"))
      (node (ref "J3") (pin "1") (pinfunction "1_1") (pintype "passive"))
      (node (ref "J3") (pin "12") (pinfunction "12_12") (pintype "passive"))
      (node (ref "J3") (pin "16") (pinfunction "16_16") (pintype "passive"))
      (node (ref "J3") (pin "2") (pinfunction "2_2") (pintype "passive"))
      (node (ref "J3") (pin "3") (pinfunction "3_3") (pintype "passive"))
      (node (ref "J3") (pin "4") (pinfunction "4_4") (pintype "passive"))
      (node (ref "J5") (pin "2") (pinfunction "2_2") (pintype "passive"))
      (node (ref "J5") (pin "4") (pinfunction "4_4") (pintype "passive"))
      (node (ref "P2") (pin "4") (pintype "passive"))
      (node (ref "P2") (pin "5") (pintype "passive"))
      (node (ref "R1") (pin "2") (pinfunction "2_2") (pintype "passive"))
      (node (ref "R14") (pin "2") (pinfunction "2_2") (pintype "passive"))
      (node (ref "R2") (pin "1") (pinfunction "1_1") (pintype "passive"))
      (node (ref "R24") (pin "2") (pinfunction "2_2") (pintype "passive"))
      (node (ref "R28") (pin "1") (pintype "passive"))
      (node (ref "R29") (pin "1") (pintype "passive"))
      (node (ref "R3") (pin "1") (pinfunction "1_1") (pintype "passive"))
      (node (ref "R7") (pin "1") (pinfunction "1_1") (pintype "passive"))
      (node (ref "S3") (pin "3") (pinfunction "3_3") (pintype "passive"))
      (node (ref "U3") (pin "14") (pinfunction "VDD33/VIO_14") (pintype "power_in"))
    )
    (net (code "88") (name "5V_in") (class "Default")
      (node (ref "F2") (pin "1") (pinfunction "1_1") (pintype "passive"))
      (node (ref "P6") (pin "A4") (pinfunction "VBUS_A4") (pintype "bidirectional"))
      (node (ref "P6") (pin "B4") (pinfunction "VBUS_B4") (pintype "bidirectional"))
      (node (ref "P7") (pin "A4") (pinfunction "VBUS_A4") (pintype "bidirectional"))
      (node (ref "P7") (pin "B4") (pinfunction "VBUS_B4") (pintype "bidirectional"))
      (node (ref "P9") (pin "A4") (pinfunction "VBUS_A4") (pintype "bidirectional"))
      (node (ref "P9") (pin "B4") (pinfunction "VBUS_B4") (pintype "bidirectional"))
    )
    (net (code "89") (name "GND") (class "Default")
      (node (ref "C1") (pin "1") (pinfunction "1_1") (pintype "passive"))
      (node (ref "C10") (pin "2") (pinfunction "2_2") (pintype "passive"))
      (node (ref "C11") (pin "1") (pinfunction "1_1") (pintype "passive"))
      (node (ref "C12") (pin "2") (pinfunction "2_2") (pintype "passive"))
      (node (ref "C13") (pin "2") (pinfunction "2_2") (pintype "passive"))
      (node (ref "C14") (pin "1") (pinfunction "1_1") (pintype "passive"))
      (node (ref "C2") (pin "1") (pinfunction "1_1") (pintype "passive"))
      (node (ref "C21") (pin "2") (pinfunction "2_2") (pintype "passive"))
      (node (ref "C3") (pin "1") (pinfunction "1_1") (pintype "passive"))
      (node (ref "C31") (pin "1") (pinfunction "1_1") (pintype "passive"))
      (node (ref "C32") (pin "1") (pinfunction "1_1") (pintype "passive"))
      (node (ref "C4") (pin "1") (pinfunction "1_1") (pintype "passive"))
      (node (ref "C5") (pin "2") (pinfunction "2_2") (pintype "passive"))
      (node (ref "C6") (pin "2") (pinfunction "2_2") (pintype "passive"))
      (node (ref "C7") (pin "1") (pinfunction "1_1") (pintype "passive"))
      (node (ref "C8") (pin "1") (pinfunction "1_1") (pintype "passive"))
      (node (ref "C9") (pin "2") (pinfunction "2_2") (pintype "passive"))
      (node (ref "J2") (pin "5") (pinfunction "5_5") (pintype "passive"))
      (node (ref "J2") (pin "6") (pinfunction "6_6") (pintype "passive"))
      (node (ref "J3") (pin "19") (pinfunction "19_19") (pintype "passive"))
      (node (ref "J3") (pin "20") (pinfunction "20_20") (pintype "passive"))
      (node (ref "J3") (pin "21") (pinfunction "21_21") (pintype "passive"))
      (node (ref "J3") (pin "22") (pinfunction "22_22") (pintype "passive"))
      (node (ref "J3") (pin "7") (pinfunction "7_7") (pintype "passive"))
      (node (ref "J3") (pin "8") (pinfunction "8_8") (pintype "passive"))
      (node (ref "J4") (pin "32") (pinfunction "32_32") (pintype "passive"))
      (node (ref "J4") (pin "7") (pinfunction "7_7") (pintype "passive"))
      (node (ref "J5") (pin "6") (pinfunction "6_6") (pintype "passive"))
      (node (ref "J5") (pin "7") (pinfunction "7_7") (pintype "passive"))
      (node (ref "J7") (pin "4") (pinfunction "4_4") (pintype "passive"))
      (node (ref "P2") (pin "8") (pintype "passive"))
      (node (ref "P6") (pin "A1") (pinfunction "GND_A1") (pintype "bidirectional"))
      (node (ref "P6") (pin "B1") (pinfunction "GND_B1") (pintype "bidirectional"))
      (node (ref "P7") (pin "A1") (pinfunction "GND_A1") (pintype "bidirectional"))
      (node (ref "P7") (pin "B1") (pinfunction "GND_B1") (pintype "bidirectional"))
      (node (ref "P9") (pin "A1") (pinfunction "GND_A1") (pintype "bidirectional"))
      (node (ref "P9") (pin "B1") (pinfunction "GND_B1") (pintype "bidirectional"))
      (node (ref "PWR") (pin "2") (pinfunction "K_2") (pintype "passive"))
      (node (ref "R10") (pin "2") (pinfunction "2_2") (pintype "passive"))
      (node (ref "R11") (pin "2") (pinfunction "2_2") (pintype "passive"))
      (node (ref "R18") (pin "1") (pinfunction "1_1") (pintype "passive"))
      (node (ref "R21") (pin "1") (pinfunction "1_1") (pintype "passive"))
      (node (ref "R22") (pin "1") (pinfunction "1_1") (pintype "passive"))
      (node (ref "R25") (pin "1") (pinfunction "1_1") (pintype "passive"))
      (node (ref "R8") (pin "1") (pinfunction "1_1") (pintype "passive"))
      (node (ref "R9") (pin "1") (pinfunction "1_1") (pintype "passive"))
      (node (ref "S1") (pin "3") (pinfunction "B1_3") (pintype "passive"))
      (node (ref "S2") (pin "3") (pinfunction "B1_3") (pintype "passive"))
      (node (ref "S5") (pin "2") (pinfunction "2_2") (pintype "passive"))
      (node (ref "U1") (pin "1") (pinfunction "GND_1") (pintype "passive"))
      (node (ref "U2") (pin "12") (pinfunction "VSSA_12") (pintype "power_in"))
      (node (ref "U2") (pin "18") (pinfunction "VSS_4_18") (pintype "power_in"))
      (node (ref "U2") (pin "31") (pinfunction "VSS_1_31") (pintype "power_in"))
      (node (ref "U2") (pin "63") (pinfunction "VSS_3_63") (pintype "power_in"))
      (node (ref "U3") (pin "18") (pinfunction "VSS/GND_18") (pintype "power_in"))
    )
    (net (code "90") (name "Net-(D2-K)") (class "Default")
      (node (ref "D2") (pin "2") (pinfunction "K_2") (pintype "passive"))
      (node (ref "R13") (pin "2") (pinfunction "2_2") (pintype "passive"))
    )
    (net (code "91") (name "Net-(D3-K)") (class "Default")
      (node (ref "D3") (pin "2") (pinfunction "K_2") (pintype "passive"))
      (node (ref "R21") (pin "2") (pinfunction "2_2") (pintype "passive"))
    )
    (net (code "92") (name "Net-(J3-Pad6)") (class "Default")
      (node (ref "J3") (pin "6") (pinfunction "6_6") (pintype "passive"))
      (node (ref "R5") (pin "1") (pinfunction "1_1") (pintype "passive"))
    )
    (net (code "93") (name "Net-(J3-Pad10)") (class "Default")
      (node (ref "J3") (pin "10") (pinfunction "10_10") (pintype "passive"))
      (node (ref "J5") (pin "1") (pinfunction "1_1") (pintype "passive"))
    )
    (net (code "94") (name "Net-(LED1-A)") (class "Default")
      (node (ref "LED1") (pin "1") (pinfunction "A_1") (pintype "passive"))
      (node (ref "R2") (pin "2") (pinfunction "2_2") (pintype "passive"))
    )
    (net (code "95") (name "Net-(LED2-A)") (class "Default")
      (node (ref "LED2") (pin "1") (pinfunction "A_1") (pintype "passive"))
      (node (ref "R3") (pin "2") (pinfunction "2_2") (pintype "passive"))
    )
    (net (code "96") (name "Net-(P2-Pad9)") (class "Default")
      (node (ref "P2") (pin "9") (pintype "passive"))
      (node (ref "R28") (pin "2") (pintype "passive"))
    )
    (net (code "97") (name "Net-(P2-Pad12)") (class "Default")
      (node (ref "P2") (pin "12") (pintype "passive"))
      (node (ref "R29") (pin "2") (pintype "passive"))
    )
    (net (code "98") (name "Net-(P6-CC-PadA5)") (class "Default")
      (node (ref "P6") (pin "A5") (pinfunction "CC_A5") (pintype "bidirectional"))
      (node (ref "R18") (pin "2") (pinfunction "2_2") (pintype "passive"))
    )
    (net (code "99") (name "Net-(P6-CC-PadB5)") (class "Default")
      (node (ref "P6") (pin "B5") (pinfunction "CC_B5") (pintype "bidirectional"))
      (node (ref "R25") (pin "2") (pinfunction "2_2") (pintype "passive"))
    )
    (net (code "100") (name "Net-(P7-CC-PadA5)") (class "Default")
      (node (ref "P7") (pin "A5") (pinfunction "CC_A5") (pintype "bidirectional"))
      (node (ref "R8") (pin "2") (pinfunction "2_2") (pintype "passive"))
    )
    (net (code "101") (name "Net-(P7-CC-PadB5)") (class "Default")
      (node (ref "P7") (pin "B5") (pinfunction "CC_B5") (pintype "bidirectional"))
      (node (ref "R9") (pin "2") (pinfunction "2_2") (pintype "passive"))
    )
    (net (code "102") (name "Net-(P9-CC-PadA5)") (class "Default")
      (node (ref "P9") (pin "A5") (pinfunction "CC_A5") (pintype "bidirectional"))
      (node (ref "R10") (pin "1") (pinfunction "1_1") (pintype "passive"))
    )
    (net (code "103") (name "Net-(P9-CC-PadB5)") (class "Default")
      (node (ref "P9") (pin "B5") (pinfunction "CC_B5") (pintype "bidirectional"))
      (node (ref "R11") (pin "1") (pinfunction "1_1") (pintype "passive"))
    )
    (net (code "104") (name "Net-(PWR-A)") (class "Default")
      (node (ref "PWR") (pin "1") (pinfunction "A_1") (pintype "passive"))
      (node (ref "R1") (pin "1") (pinfunction "1_1") (pintype "passive"))
    )
    (net (code "105") (name "Net-(U1-VOUT)") (class "Default")
      (node (ref "C13") (pin "1") (pinfunction "1_1") (pintype "passive"))
      (node (ref "S3") (pin "1") (pinfunction "1_1") (pintype "passive"))
      (node (ref "U1") (pin "2") (pinfunction "VOUT_2") (pintype "passive"))
    )
    (net (code "106") (name "Net-(U2-VDD_2)") (class "Default")
      (node (ref "R16") (pin "2") (pinfunction "2_2") (pintype "passive"))
      (node (ref "U2") (pin "48") (pinfunction "VDD_2_48") (pintype "power_in"))
    )
    (net (code "107") (name "Net-(U2-VSS_2)") (class "Default")
      (node (ref "R22") (pin "2") (pinfunction "2_2") (pintype "passive"))
      (node (ref "U2") (pin "47") (pinfunction "VSS_2_47") (pintype "power_in"))
    )
    (net (code "108") (name "unconnected-(P2-Pad7)") (class "Default")
      (node (ref "P2") (pin "7") (pintype "passive"))
    )
    (net (code "109") (name "unconnected-(P6-RFU1-PadA8)") (class "Default")
      (node (ref "P6") (pin "A8") (pinfunction "RFU1_A8") (pintype "bidirectional+no_connect"))
    )
    (net (code "110") (name "unconnected-(P6-RFU1-PadB8)") (class "Default")
      (node (ref "P6") (pin "B8") (pinfunction "RFU1_B8") (pintype "bidirectional+no_connect"))
    )
    (net (code "111") (name "unconnected-(P7-RFU1-PadA8)") (class "Default")
      (node (ref "P7") (pin "A8") (pinfunction "RFU1_A8") (pintype "bidirectional+no_connect"))
    )
    (net (code "112") (name "unconnected-(P7-RFU1-PadB8)") (class "Default")
      (node (ref "P7") (pin "B8") (pinfunction "RFU1_B8") (pintype "bidirectional+no_connect"))
    )
    (net (code "113") (name "unconnected-(P9-RFU1-PadA8)") (class "Default")
      (node (ref "P9") (pin "A8") (pinfunction "RFU1_A8") (pintype "bidirectional+no_connect"))
    )
    (net (code "114") (name "unconnected-(P9-RFU1-PadB8)") (class "Default")
      (node (ref "P9") (pin "B8") (pinfunction "RFU1_B8") (pintype "bidirectional+no_connect"))
    )
    (net (code "115") (name "unconnected-(S1-A1-Pad4)") (class "Default")
      (node (ref "S1") (pin "4") (pinfunction "A1_4") (pintype "passive"))
    )
    (net (code "116") (name "unconnected-(S1-B0-Pad2)") (class "Default")
      (node (ref "S1") (pin "2") (pinfunction "B0_2") (pintype "passive"))
    )
    (net (code "117") (name "unconnected-(S2-A1-Pad4)") (class "Default")
      (node (ref "S2") (pin "4") (pinfunction "A1_4") (pintype "passive"))
    )
    (net (code "118") (name "unconnected-(S2-B0-Pad2)") (class "Default")
      (node (ref "S2") (pin "2") (pinfunction "B0_2") (pintype "passive"))
    )
    (net (code "119") (name "unconnected-(S3-Pad2)") (class "Default")
      (node (ref "S3") (pin "2") (pinfunction "2_2") (pintype "passive"))
    )
    (net (code "120") (name "unconnected-(U3-PA5{slash}UART1_CTS{slash}PA1_(no5V)-Pad2)") (class "Default")
      (node (ref "U3") (pin "2") (pinfunction "PA5/UART1_CTS/PA1_(no5V)_2") (pintype "bidirectional+no_connect"))
    )
    (net (code "121") (name "unconnected-(U3-PB12{slash}SPI2_NSS{slash}CAN2_RX-Pad5)") (class "Default")
      (node (ref "U3") (pin "5") (pinfunction "PB12/SPI2_NSS/CAN2_RX_5") (pintype "bidirectional+no_connect"))
    )
    (net (code "122") (name "unconnected-(U3-PB14{slash}SPI2_MISO{slash}UART3_RTS-Pad7)") (class "Default")
      (node (ref "U3") (pin "7") (pinfunction "PB14/SPI2_MISO/UART3_RTS_7") (pintype "bidirectional+no_connect"))
    )
    (net (code "123") (name "unconnected-(U3-PB15{slash}SPI2_MOSI{slash}UART1_TX-Pad8)") (class "Default")
      (node (ref "U3") (pin "8") (pinfunction "PB15/SPI2_MOSI/UART1_TX_8") (pintype "bidirectional+no_connect"))
    )
  )
)
